# untitled.net
KiCad netlist of a schematic drawn in EAGLE
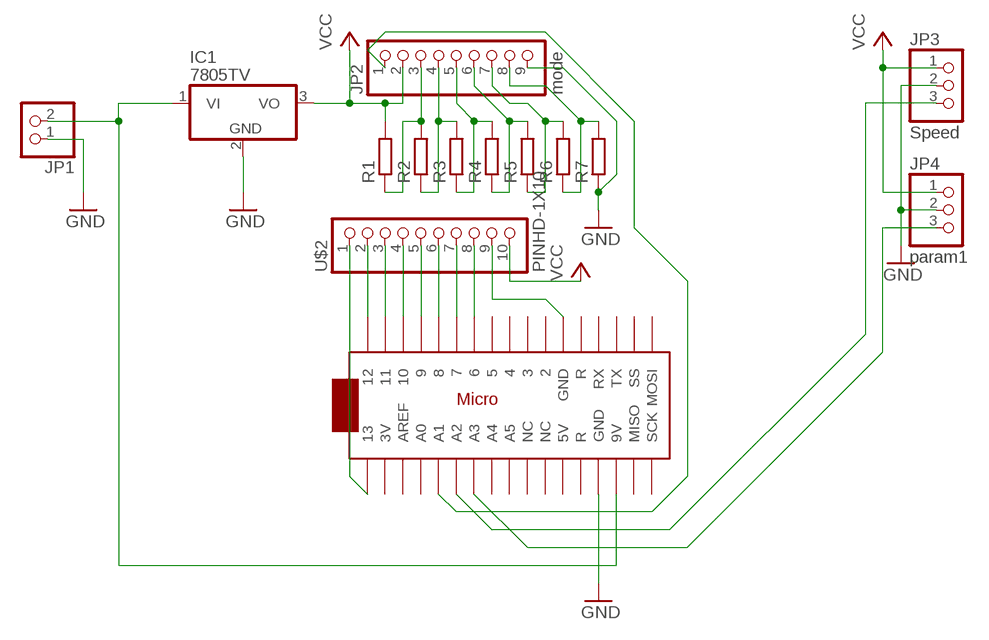
[diagram p0: schematic, sheet 1]

(export (version "E")
  (design (tool "Eeschema 10.0.6"))
  (components
    (comp (ref "IC1")
      (value "7805TV")
      (footprint "eagle-import:TO220V")
      (libsource (lib "eagle-import") (part "78TV05"))
    )
    (comp (ref "JP1")
      (value "PINHD-1X2")
      (footprint "eagle-import:1X02")
      (libsource (lib "eagle-import") (part "PINHD-1X2"))
    )
    (comp (ref "JP2")
      (value "mode")
      (footprint "eagle-import:1X09-BIG")
      (libsource (lib "eagle-import") (part "PINHD-1X9"))
    )
    (comp (ref "JP3")
      (value "Speed")
      (footprint "eagle-import:1X03")
      (libsource (lib "eagle-import") (part "PINHD-1X3"))
    )
    (comp (ref "JP4")
      (value "param1")
      (footprint "eagle-import:1X03")
      (libsource (lib "eagle-import") (part "PINHD-1X3"))
    )
    (comp (ref "R1")
      (value "R-EU_0204/7")
      (footprint "eagle-import:0204_7")
      (libsource (lib "eagle-import") (part "R-EU_0204/7"))
    )
    (comp (ref "R2")
      (value "R-EU_0204/7")
      (footprint "eagle-import:0204_7")
      (libsource (lib "eagle-import") (part "R-EU_0204/7"))
    )
    (comp (ref "R3")
      (value "R-EU_0204/7")
      (footprint "eagle-import:0204_7")
      (libsource (lib "eagle-import") (part "R-EU_0204/7"))
    )
    (comp (ref "R4")
      (value "R-EU_0204/7")
      (footprint "eagle-import:0204_7")
      (libsource (lib "eagle-import") (part "R-EU_0204/7"))
    )
    (comp (ref "R5")
      (value "R-EU_0204/7")
      (footprint "eagle-import:0204_7")
      (libsource (lib "eagle-import") (part "R-EU_0204/7"))
    )
    (comp (ref "R6")
      (value "R-EU_0204/7")
      (footprint "eagle-import:0204_7")
      (libsource (lib "eagle-import") (part "R-EU_0204/7"))
    )
    (comp (ref "R7")
      (value "R-EU_0204/7")
      (footprint "eagle-import:0204_7")
      (libsource (lib "eagle-import") (part "R-EU_0204/7"))
    )
    (comp (ref "U$1")
      (value "ARDUINOMICRO")
      (footprint "eagle-import:ARDUINOMICRO")
      (libsource (lib "eagle-import") (part "ARDUINOMICRO"))
    )
    (comp (ref "U$2")
      (value "PINHD-1X10")
      (footprint "eagle-import:1X10-BIG")
      (libsource (lib "eagle-import") (part "PINHD-1X10"))
    )
  )
  (nets
    (net (code "1") (name "GND") (class "Default")
      (node (ref "IC1") (pin "2") (pinfunction "GND_2") (pintype "passive"))
      (node (ref "JP1") (pin "1") (pinfunction "1_1") (pintype "passive"))
      (node (ref "JP2") (pin "9") (pinfunction "9_9") (pintype "passive"))
      (node (ref "JP3") (pin "2") (pinfunction "2_2") (pintype "passive"))
      (node (ref "JP4") (pin "2") (pinfunction "2_2") (pintype "passive"))
      (node (ref "R7") (pin "1") (pinfunction "1_1") (pintype "passive"))
      (node (ref "U$1") (pin "P$12") (pinfunction "GND_P$12") (pintype "bidirectional"))
    )
    (net (code "2") (name "Net-(IC1-VI)") (class "Default")
      (node (ref "IC1") (pin "1") (pinfunction "VI_1") (pintype "input"))
      (node (ref "JP1") (pin "2") (pinfunction "2_2") (pintype "passive"))
      (node (ref "U$1") (pin "P$20") (pinfunction "9V_P$20") (pintype "bidirectional"))
    )
    (net (code "3") (name "Net-(JP2-Pad3)") (class "Default")
      (node (ref "JP2") (pin "3") (pinfunction "3_3") (pintype "passive"))
      (node (ref "R1") (pin "1") (pinfunction "1_1") (pintype "passive"))
      (node (ref "R2") (pin "2") (pinfunction "2_2") (pintype "passive"))
    )
    (net (code "4") (name "Net-(JP2-Pad4)") (class "Default")
      (node (ref "JP2") (pin "4") (pinfunction "4_4") (pintype "passive"))
      (node (ref "R2") (pin "1") (pinfunction "1_1") (pintype "passive"))
      (node (ref "R3") (pin "2") (pinfunction "2_2") (pintype "passive"))
    )
    (net (code "5") (name "Net-(JP2-Pad5)") (class "Default")
      (node (ref "JP2") (pin "5") (pinfunction "5_5") (pintype "passive"))
      (node (ref "R3") (pin "1") (pinfunction "1_1") (pintype "passive"))
      (node (ref "R4") (pin "2") (pinfunction "2_2") (pintype "passive"))
    )
    (net (code "6") (name "Net-(JP2-Pad6)") (class "Default")
      (node (ref "JP2") (pin "6") (pinfunction "6_6") (pintype "passive"))
      (node (ref "R4") (pin "1") (pinfunction "1_1") (pintype "passive"))
      (node (ref "R5") (pin "2") (pinfunction "2_2") (pintype "passive"))
    )
    (net (code "7") (name "Net-(JP2-Pad7)") (class "Default")
      (node (ref "JP2") (pin "7") (pinfunction "7_7") (pintype "passive"))
      (node (ref "R5") (pin "1") (pinfunction "1_1") (pintype "passive"))
      (node (ref "R6") (pin "2") (pinfunction "2_2") (pintype "passive"))
    )
    (net (code "8") (name "Net-(JP2-Pad8)") (class "Default")
      (node (ref "JP2") (pin "8") (pinfunction "8_8") (pintype "passive"))
      (node (ref "R6") (pin "1") (pinfunction "1_1") (pintype "passive"))
      (node (ref "R7") (pin "2") (pinfunction "2_2") (pintype "passive"))
    )
    (net (code "9") (name "Net-(U$1-6)") (class "Default")
      (node (ref "U$1") (pin "P$7") (pinfunction "6_P$7") (pintype "bidirectional"))
      (node (ref "U$2") (pin "8") (pinfunction "8_8") (pintype "passive"))
    )
    (net (code "10") (name "Net-(U$1-7)") (class "Default")
      (node (ref "U$1") (pin "P$6") (pinfunction "7_P$6") (pintype "bidirectional"))
      (node (ref "U$2") (pin "7") (pinfunction "7_7") (pintype "passive"))
    )
    (net (code "11") (name "Net-(U$1-8)") (class "Default")
      (node (ref "U$1") (pin "P$5") (pinfunction "8_P$5") (pintype "bidirectional"))
      (node (ref "U$2") (pin "6") (pinfunction "6_6") (pintype "passive"))
    )
    (net (code "12") (name "Net-(U$1-9)") (class "Default")
      (node (ref "U$1") (pin "P$4") (pinfunction "9_P$4") (pintype "bidirectional"))
      (node (ref "U$2") (pin "5") (pinfunction "5_5") (pintype "passive"))
    )
    (net (code "13") (name "Net-(U$1-10)") (class "Default")
      (node (ref "U$1") (pin "P$3") (pinfunction "10_P$3") (pintype "bidirectional"))
      (node (ref "U$2") (pin "4") (pinfunction "4_4") (pintype "passive"))
    )
    (net (code "14") (name "Net-(U$1-11)") (class "Default")
      (node (ref "U$1") (pin "P$2") (pinfunction "11_P$2") (pintype "bidirectional"))
      (node (ref "U$2") (pin "3") (pinfunction "3_3") (pintype "passive"))
    )
    (net (code "15") (name "Net-(U$1-12)") (class "Default")
      (node (ref "U$1") (pin "P$1") (pinfunction "12_P$1") (pintype "bidirectional"))
      (node (ref "U$2") (pin "2") (pinfunction "2_2") (pintype "passive"))
    )
    (net (code "16") (name "Net-(U$1-13)") (class "Default")
      (node (ref "U$1") (pin "P$34") (pinfunction "13_P$34") (pintype "bidirectional"))
      (node (ref "U$2") (pin "1") (pinfunction "1_1") (pintype "passive"))
    )
    (net (code "17") (name "Net-(U$1-A1)") (class "Default")
      (node (ref "JP2") (pin "1") (pinfunction "1_1") (pintype "passive"))
      (node (ref "U$1") (pin "P$30") (pinfunction "A1_P$30") (pintype "bidirectional"))
    )
    (net (code "18") (name "Net-(U$1-A2)") (class "Default")
      (node (ref "JP3") (pin "3") (pinfunction "3_3") (pintype "passive"))
      (node (ref "U$1") (pin "P$29") (pinfunction "A2_P$29") (pintype "bidirectional"))
    )
    (net (code "19") (name "Net-(U$1-A3)") (class "Default")
      (node (ref "JP4") (pin "3") (pinfunction "3_3") (pintype "passive"))
      (node (ref "U$1") (pin "P$28") (pinfunction "A3_P$28") (pintype "bidirectional"))
    )
    (net (code "20") (name "Net-(U$1-GND-PadP$21)") (class "Default")
      (node (ref "U$1") (pin "P$21") (pinfunction "GND_P$21") (pintype "bidirectional"))
      (node (ref "U$2") (pin "9") (pinfunction "9_9") (pintype "passive"))
    )
    (net (code "21") (name "VCC") (class "Default")
      (node (ref "IC1") (pin "3") (pinfunction "VO_3") (pintype "passive"))
      (node (ref "JP2") (pin "2") (pinfunction "2_2") (pintype "passive"))
      (node (ref "JP3") (pin "1") (pinfunction "1_1") (pintype "passive"))
      (node (ref "JP4") (pin "1") (pinfunction "1_1") (pintype "passive"))
      (node (ref "R1") (pin "2") (pinfunction "2_2") (pintype "passive"))
      (node (ref "U$2") (pin "10") (pinfunction "10_10") (pintype "passive"))
    )
    (net (code "22") (name "unconnected-(U$1-2-PadP$11)") (class "Default")
      (node (ref "U$1") (pin "P$11") (pinfunction "2_P$11") (pintype "bidirectional"))
    )
    (net (code "23") (name "unconnected-(U$1-3-PadP$10)") (class "Default")
      (node (ref "U$1") (pin "P$10") (pinfunction "3_P$10") (pintype "bidirectional"))
    )
    (net (code "24") (name "unconnected-(U$1-3V-PadP$33)") (class "Default")
      (node (ref "U$1") (pin "P$33") (pinfunction "3V_P$33") (pintype "bidirectional"))
    )
    (net (code "25") (name "unconnected-(U$1-4-PadP$9)") (class "Default")
      (node (ref "U$1") (pin "P$9") (pinfunction "4_P$9") (pintype "bidirectional"))
    )
    (net (code "26") (name "unconnected-(U$1-5-PadP$8)") (class "Default")
      (node (ref "U$1") (pin "P$8") (pinfunction "5_P$8") (pintype "bidirectional"))
    )
    (net (code "27") (name "unconnected-(U$1-5V-PadP$23)") (class "Default")
      (node (ref "U$1") (pin "P$23") (pinfunction "5V_P$23") (pintype "bidirectional"))
    )
    (net (code "28") (name "unconnected-(U$1-A0-PadP$31)") (class "Default")
      (node (ref "U$1") (pin "P$31") (pinfunction "A0_P$31") (pintype "bidirectional"))
    )
    (net (code "29") (name "unconnected-(U$1-A4-PadP$27)") (class "Default")
      (node (ref "U$1") (pin "P$27") (pinfunction "A4_P$27") (pintype "bidirectional"))
    )
    (net (code "30") (name "unconnected-(U$1-A5-PadP$26)") (class "Default")
      (node (ref "U$1") (pin "P$26") (pinfunction "A5_P$26") (pintype "bidirectional"))
    )
    (net (code "31") (name "unconnected-(U$1-AREF-PadP$32)") (class "Default")
      (node (ref "U$1") (pin "P$32") (pinfunction "AREF_P$32") (pintype "bidirectional"))
    )
    (net (code "32") (name "unconnected-(U$1-MISO-PadP$19)") (class "Default")
      (node (ref "U$1") (pin "P$19") (pinfunction "MISO_P$19") (pintype "bidirectional"))
    )
    (net (code "33") (name "unconnected-(U$1-MOSI-PadP$17)") (class "Default")
      (node (ref "U$1") (pin "P$17") (pinfunction "MOSI_P$17") (pintype "bidirectional"))
    )
    (net (code "34") (name "unconnected-(U$1-NC-PadP$24)") (class "Default")
      (node (ref "U$1") (pin "P$24") (pinfunction "NC_P$24") (pintype "bidirectional"))
    )
    (net (code "35") (name "unconnected-(U$1-NC-PadP$25)") (class "Default")
      (node (ref "U$1") (pin "P$25") (pinfunction "NC_P$25") (pintype "bidirectional"))
    )
    (net (code "36") (name "unconnected-(U$1-R-PadP$13)") (class "Default")
      (node (ref "U$1") (pin "P$13") (pinfunction "R_P$13") (pintype "bidirectional"))
    )
    (net (code "37") (name "unconnected-(U$1-R-PadP$22)") (class "Default")
      (node (ref "U$1") (pin "P$22") (pinfunction "R_P$22") (pintype "bidirectional"))
    )
    (net (code "38") (name "unconnected-(U$1-RX-PadP$14)") (class "Default")
      (node (ref "U$1") (pin "P$14") (pinfunction "RX_P$14") (pintype "bidirectional"))
    )
    (net (code "39") (name "unconnected-(U$1-SCK-PadP$18)") (class "Default")
      (node (ref "U$1") (pin "P$18") (pinfunction "SCK_P$18") (pintype "bidirectional"))
    )
    (net (code "40") (name "unconnected-(U$1-SS-PadP$16)") (class "Default")
      (node (ref "U$1") (pin "P$16") (pinfunction "SS_P$16") (pintype "bidirectional"))
    )
    (net (code "41") (name "unconnected-(U$1-TX-PadP$15)") (class "Default")
      (node (ref "U$1") (pin "P$15") (pinfunction "TX_P$15") (pintype "bidirectional"))
    )
  )
)
